# Schematic.net
KiCad netlist of a schematic drawn in Altium Designer
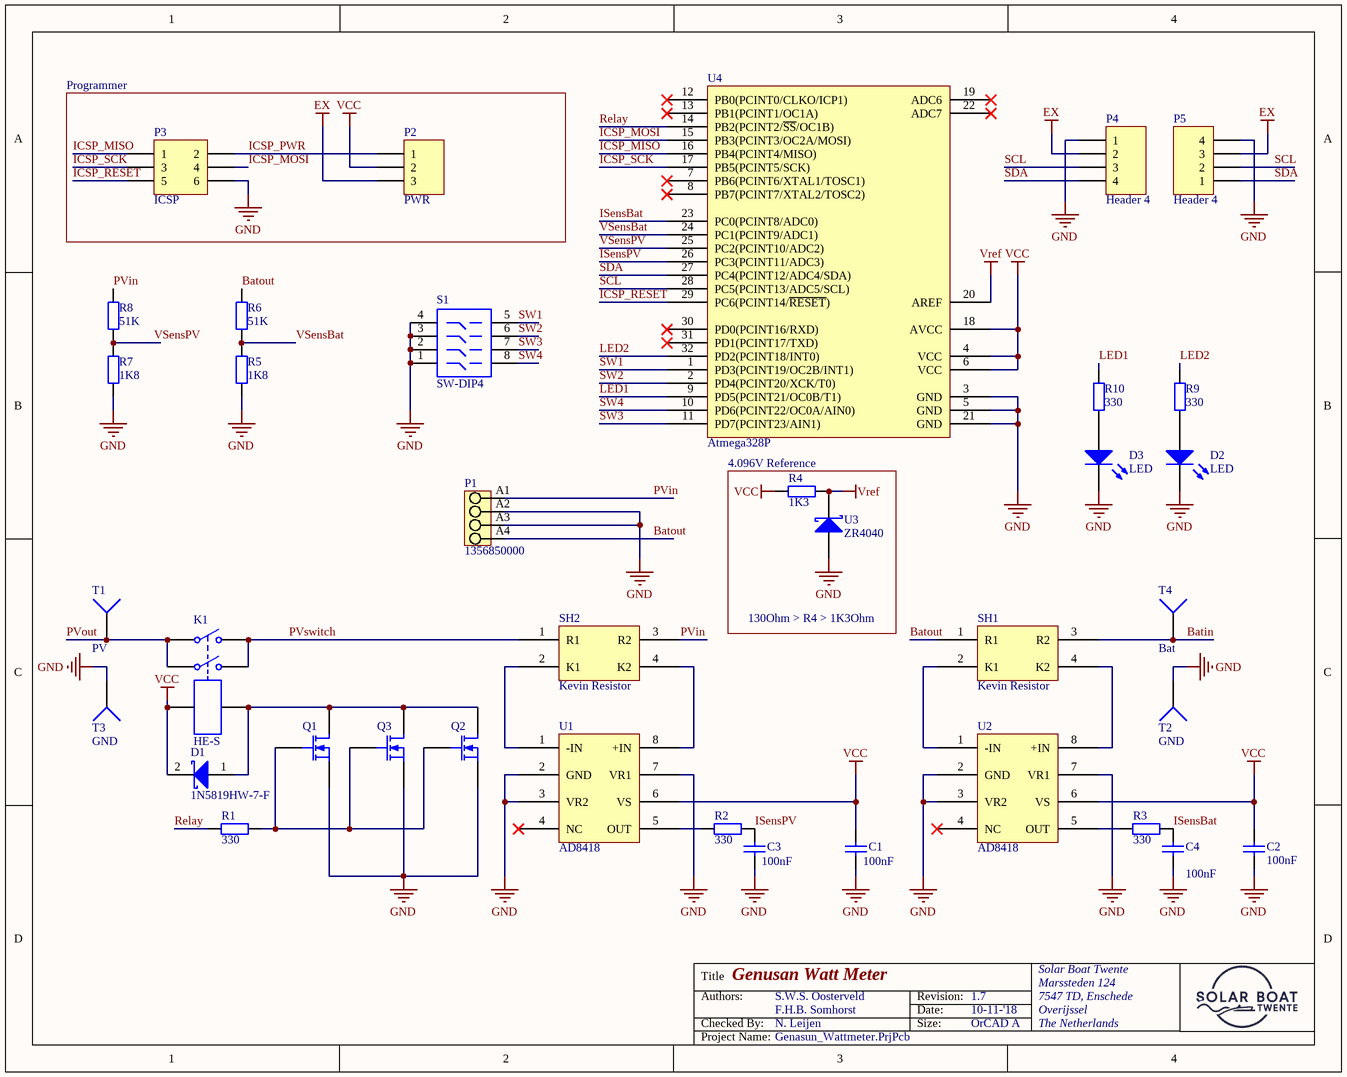
[diagram p0: Schematic.SchDoc]

(export (version "E")
  (design (tool "Eeschema 10.0.6"))
  (components
    (comp (ref "C1")
      (value "100nF")
      (footprint "CAP 0805/2012")
      (description "Capacitor")
      (fields (field (name "Comment") "Cap") (field (name "PUBLISHER") "Altium Limited"))
      (libsource (lib "Miscellaneous Devices") (part "Cap"))
    )
    (comp (ref "C2")
      (value "100nF")
      (footprint "CAP 0805/2012")
      (description "Capacitor")
      (fields (field (name "Comment") "Cap") (field (name "PUBLISHER") "Altium Limited"))
      (libsource (lib "Miscellaneous Devices") (part "Cap"))
    )
    (comp (ref "C3")
      (value "100nF")
      (footprint "CAP 0805/2012")
      (description "Capacitor")
      (fields (field (name "Comment") "Cap") (field (name "PUBLISHER") "Altium Limited"))
      (libsource (lib "Miscellaneous Devices") (part "Cap"))
    )
    (comp (ref "C4")
      (value "100nF")
      (footprint "CAP 0805/2012")
      (description "Capacitor")
      (fields (field (name "Comment") "Cap") (field (name "PUBLISHER") "Altium Limited"))
      (libsource (lib "Miscellaneous Devices") (part "Cap"))
    )
    (comp (ref "D1")
      (value "1N5819HW-7-F")
      (footprint "DIOD-SOD-123-2_V")
      (fields (field (name "MANUFACTURER") "Diodes Inc"))
      (libsource (lib "Altium Content Vault") (part "DIOD-DSKY-A1K2-2"))
    )
    (comp (ref "D2")
      (value "LED")
      (footprint "LED 0805/2012 RED")
      (description "Typical INFRARED GaAs LED")
      (fields (field (name "PUBLISHER") "Altium Limited"))
      (libsource (lib "Miscellaneous Devices") (part "LED0"))
    )
    (comp (ref "D3")
      (value "LED")
      (footprint "LED 0805/2012 RED")
      (description "Typical INFRARED GaAs LED")
      (fields (field (name "PUBLISHER") "Altium Limited"))
      (libsource (lib "Miscellaneous Devices") (part "LED0"))
    )
    (comp (ref "K1")
      (value "HE-S")
      (footprint "Relay HE-S Parasonic")
      (description "Dual-Pole Single-Throw Relay")
      (fields (field (name "PUBLISHER") "Altium Limited"))
      (libsource (lib "Miscellaneous Devices") (part "Relay-DPST"))
    )
    (comp (ref "P1")
      (value "1356850000")
      (footprint "LL_6_35_90V_04")
      (description "OMNIMATE Signal - series LL")
      (fields (field (name "MANUFACTURER") "Weidmueller"))
      (libsource (lib "Altium Content Vault") (part "Terminal_04_1x04"))
    )
    (comp (ref "P2")
      (value "PWR")
      (footprint "HDR1X3")
      (description "Header, 3-Pin")
      (fields (field (name "PUBLISHER") "Altium Limited"))
      (libsource (lib "Miscellaneous Connectors") (part "Header 3"))
    )
    (comp (ref "P3")
      (value "ICSP")
      (footprint "HDR2X3")
      (description "Header, 3-Pin, Dual row")
      (fields (field (name "PUBLISHER") "Altium Limited"))
      (libsource (lib "Miscellaneous Connectors") (part "Header 3X2"))
    )
    (comp (ref "P4")
      (value "Header 4")
      (footprint "TE 282834-4")
      (description "Header, 4-Pin")
      (fields (field (name "PUBLISHER") "Altium Limited"))
      (libsource (lib "Miscellaneous Connectors") (part "Header 4"))
    )
    (comp (ref "P5")
      (value "Header 4")
      (footprint "TE 282834-4")
      (description "Header, 4-Pin")
      (fields (field (name "PUBLISHER") "Altium Limited"))
      (libsource (lib "") (part "Header 4_1"))
    )
    (comp (ref "Q1")
      (value "MOSFET-N")
      (footprint "DIODES SOT-23-3")
      (description "N-Channel MOSFET")
      (fields (field (name "PUBLISHER") "Altium Limited"))
      (libsource (lib "Miscellaneous Devices") (part "MOSFET-N"))
    )
    (comp (ref "Q2")
      (value "MOSFET-N")
      (footprint "DIODES SOT-23-3")
      (description "N-Channel MOSFET")
      (fields (field (name "PUBLISHER") "Altium Limited"))
      (libsource (lib "Miscellaneous Devices") (part "MOSFET-N"))
    )
    (comp (ref "Q3")
      (value "MOSFET-N")
      (footprint "DIODES SOT-23-3")
      (description "N-Channel MOSFET")
      (fields (field (name "PUBLISHER") "Altium Limited"))
      (libsource (lib "Miscellaneous Devices") (part "MOSFET-N"))
    )
    (comp (ref "R1")
      (value "330")
      (footprint "RES 0805/2012")
      (description "Resistor")
      (fields (field (name "Comment") "Res2") (field (name "PUBLISHER") "Altium Limited"))
      (libsource (lib "") (part "Res2_1"))
    )
    (comp (ref "R2")
      (value "330")
      (footprint "RES 0805/2012")
      (description "Resistor")
      (fields (field (name "Comment") "Res2") (field (name "PUBLISHER") "Altium Limited"))
      (libsource (lib "") (part "Res2_1"))
    )
    (comp (ref "R3")
      (value "330")
      (footprint "RES 0805/2012")
      (description "Resistor")
      (fields (field (name "Comment") "Res2") (field (name "PUBLISHER") "Altium Limited"))
      (libsource (lib "") (part "Res2_1"))
    )
    (comp (ref "R4")
      (value "1K3")
      (footprint "RES 0805/2012")
      (description "Resistor")
      (fields (field (name "Comment") "Res2") (field (name "PUBLISHER") "Altium Limited"))
      (libsource (lib "") (part "Res2_1"))
    )
    (comp (ref "R5")
      (value "1K8")
      (footprint "RES 0805/2012")
      (description "Resistor")
      (fields (field (name "Comment") "Res2") (field (name "PUBLISHER") "Altium Limited"))
      (libsource (lib "Miscellaneous Devices") (part "Res2"))
    )
    (comp (ref "R6")
      (value "51K")
      (footprint "RES 0805/2012")
      (description "Resistor")
      (fields (field (name "Comment") "Res2") (field (name "PUBLISHER") "Altium Limited"))
      (libsource (lib "Miscellaneous Devices") (part "Res2"))
    )
    (comp (ref "R7")
      (value "1K8")
      (footprint "RES 0805/2012")
      (description "Resistor")
      (fields (field (name "Comment") "Res2") (field (name "PUBLISHER") "Altium Limited"))
      (libsource (lib "Miscellaneous Devices") (part "Res2"))
    )
    (comp (ref "R8")
      (value "51K")
      (footprint "RES 0805/2012")
      (description "Resistor")
      (fields (field (name "Comment") "Res2") (field (name "PUBLISHER") "Altium Limited"))
      (libsource (lib "Miscellaneous Devices") (part "Res2"))
    )
    (comp (ref "R9")
      (value "330")
      (footprint "RES 0805/2012")
      (description "Resistor")
      (fields (field (name "Comment") "Res2") (field (name "PUBLISHER") "Altium Limited"))
      (libsource (lib "Miscellaneous Devices") (part "Res2"))
    )
    (comp (ref "R10")
      (value "330")
      (footprint "RES 0805/2012")
      (description "Resistor")
      (fields (field (name "Comment") "Res2") (field (name "PUBLISHER") "Altium Limited"))
      (libsource (lib "Miscellaneous Devices") (part "Res2"))
    )
    (comp (ref "S1")
      (value "SW-DIP4")
      (footprint "DIP-8")
      (description "DIP Switch")
      (fields (field (name "PUBLISHER") "Altium Limited"))
      (libsource (lib "Miscellaneous Devices") (part "SW-DIP4"))
    )
    (comp (ref "SH1")
      (value "Kevin Resistor")
      (footprint "TE TLR Shunt")
      (libsource (lib "Personal Library") (part "Kevin Resistor"))
    )
    (comp (ref "SH2")
      (value "Kevin Resistor")
      (footprint "TE TLR Shunt")
      (libsource (lib "Personal Library") (part "Kevin Resistor"))
    )
    (comp (ref "T1")
      (value "PV")
      (footprint "PCB_Pin_Outsteeksel")
      (description "Socket")
      (fields (field (name "PUBLISHER") "Altium Limited"))
      (libsource (lib "Miscellaneous Connectors") (part "Socket"))
    )
    (comp (ref "T2")
      (value "GND")
      (footprint "PCB_Pin_Outsteeksel")
      (description "Socket")
      (fields (field (name "PUBLISHER") "Altium Limited"))
      (libsource (lib "Miscellaneous Connectors") (part "Socket"))
    )
    (comp (ref "T3")
      (value "GND")
      (footprint "PCB_Pin_Outsteeksel")
      (description "Socket")
      (fields (field (name "PUBLISHER") "Altium Limited"))
      (libsource (lib "Miscellaneous Connectors") (part "Socket"))
    )
    (comp (ref "T4")
      (value "Bat")
      (footprint "PCB_Pin_Outsteeksel")
      (description "Socket")
      (fields (field (name "PUBLISHER") "Altium Limited"))
      (libsource (lib "Miscellaneous Connectors") (part "Socket"))
    )
    (comp (ref "U1")
      (value "AD8418")
      (footprint "INTERSIL MSOP-8 M8.118")
      (libsource (lib "GJ24") (part "AD8418"))
    )
    (comp (ref "U2")
      (value "AD8418")
      (footprint "INTERSIL MSOP-8 M8.118")
      (libsource (lib "GJ24") (part "AD8418"))
    )
    (comp (ref "U3")
      (value "ZR4040")
      (footprint "DIODES SOT-23-3")
      (description "Schottky Rectifier")
      (fields (field (name "PUBLISHER") "Altium Limited"))
      (libsource (lib "Miscellaneous Devices") (part "Diode 10TQ035"))
    )
    (comp (ref "U4")
      (value "Atmega328P")
      (footprint "ST LQFP-32 7X7MM")
      (libsource (lib "GJ24") (part "Atmega328P"))
    )
  )
  (nets
    (net (code "1") (name "/Batin") (class "Default")
      (node (ref "SH1") (pin "3") (pinfunction "R2_3") (pintype "passive"))
      (node (ref "T4") (pin "1") (pinfunction "1_1") (pintype "passive"))
    )
    (net (code "2") (name "/Batout") (class "Default")
      (node (ref "P1") (pin "A4") (pinfunction "A4_A4") (pintype "passive"))
      (node (ref "R6") (pin "2") (pinfunction "2_2") (pintype "passive"))
      (node (ref "SH1") (pin "1") (pinfunction "R1_1") (pintype "passive"))
    )
    (net (code "3") (name "/ICSP_MISO") (class "Default")
      (node (ref "P3") (pin "1") (pinfunction "1_1") (pintype "passive"))
      (node (ref "U4") (pin "16") (pinfunction "PB4(PCINT4/MISO)_16") (pintype "passive"))
    )
    (net (code "4") (name "/ICSP_MOSI") (class "Default")
      (node (ref "P3") (pin "4") (pinfunction "4_4") (pintype "passive"))
      (node (ref "U4") (pin "15") (pinfunction "PB3(PCINT3/OC2A/MOSI)_15") (pintype "passive"))
    )
    (net (code "5") (name "/ICSP_PWR") (class "Default")
      (node (ref "P2") (pin "1") (pinfunction "1_1") (pintype "passive"))
      (node (ref "P3") (pin "2") (pinfunction "2_2") (pintype "passive"))
    )
    (net (code "6") (name "/ICSP_RESET") (class "Default")
      (node (ref "P3") (pin "5") (pinfunction "5_5") (pintype "passive"))
      (node (ref "U4") (pin "29") (pinfunction "PC6(PCINT14/~{RESET})_29") (pintype "passive"))
    )
    (net (code "7") (name "/ICSP_SCK") (class "Default")
      (node (ref "P3") (pin "3") (pinfunction "3_3") (pintype "passive"))
      (node (ref "U4") (pin "17") (pinfunction "PB5(PCINT5/SCK)_17") (pintype "passive"))
    )
    (net (code "8") (name "/ISensBat") (class "Default")
      (node (ref "C4") (pin "2") (pinfunction "2_2") (pintype "passive"))
      (node (ref "R3") (pin "1") (pinfunction "1_1") (pintype "passive"))
      (node (ref "U4") (pin "23") (pinfunction "PC0(PCINT8/ADC0)_23") (pintype "passive"))
    )
    (net (code "9") (name "/ISensPV") (class "Default")
      (node (ref "C3") (pin "2") (pinfunction "2_2") (pintype "passive"))
      (node (ref "R2") (pin "1") (pinfunction "1_1") (pintype "passive"))
      (node (ref "U4") (pin "26") (pinfunction "PC3(PCINT11/ADC3)_26") (pintype "passive"))
    )
    (net (code "10") (name "/LED1") (class "Default")
      (node (ref "R10") (pin "2") (pinfunction "2_2") (pintype "passive"))
      (node (ref "U4") (pin "9") (pinfunction "PD5(PCINT21/OC0B/T1)_9") (pintype "passive"))
    )
    (net (code "11") (name "/LED2") (class "Default")
      (node (ref "R9") (pin "2") (pinfunction "2_2") (pintype "passive"))
      (node (ref "U4") (pin "32") (pinfunction "PD2(PCINT18/INT0)_32") (pintype "passive"))
    )
    (net (code "12") (name "/PVin") (class "Default")
      (node (ref "P1") (pin "A1") (pinfunction "A1_A1") (pintype "passive"))
      (node (ref "R8") (pin "2") (pinfunction "2_2") (pintype "passive"))
      (node (ref "SH2") (pin "3") (pinfunction "R2_3") (pintype "passive"))
    )
    (net (code "13") (name "/PVout") (class "Default")
      (node (ref "K1") (pin "1") (pinfunction "1_1") (pintype "passive"))
      (node (ref "K1") (pin "3") (pinfunction "3_3") (pintype "passive"))
      (node (ref "T1") (pin "1") (pinfunction "1_1") (pintype "passive"))
    )
    (net (code "14") (name "/PVswitch") (class "Default")
      (node (ref "K1") (pin "2") (pinfunction "2_2") (pintype "passive"))
      (node (ref "K1") (pin "4") (pinfunction "4_4") (pintype "passive"))
      (node (ref "SH2") (pin "1") (pinfunction "R1_1") (pintype "passive"))
    )
    (net (code "15") (name "/Relay") (class "Default")
      (node (ref "R1") (pin "2") (pinfunction "2_2") (pintype "passive"))
      (node (ref "U4") (pin "14") (pinfunction "PB2(PCINT2/~{SS}/OC1B)_14") (pintype "passive"))
    )
    (net (code "16") (name "/SCL") (class "Default")
      (node (ref "P4") (pin "3") (pinfunction "3_3") (pintype "passive"))
      (node (ref "P5") (pin "2") (pinfunction "2_2") (pintype "passive"))
      (node (ref "U4") (pin "28") (pinfunction "PC5(PCINT13/ADC5/SCL)_28") (pintype "passive"))
    )
    (net (code "17") (name "/SDA") (class "Default")
      (node (ref "P4") (pin "4") (pinfunction "4_4") (pintype "passive"))
      (node (ref "P5") (pin "1") (pinfunction "1_1") (pintype "passive"))
      (node (ref "U4") (pin "27") (pinfunction "PC4(PCINT12/ADC4/SDA)_27") (pintype "passive"))
    )
    (net (code "18") (name "/SW1") (class "Default")
      (node (ref "S1") (pin "5") (pinfunction "5_5") (pintype "passive"))
      (node (ref "U4") (pin "1") (pinfunction "PD3(PCINT19/OC2B/INT1)_1") (pintype "passive"))
    )
    (net (code "19") (name "/SW2") (class "Default")
      (node (ref "S1") (pin "6") (pinfunction "6_6") (pintype "passive"))
      (node (ref "U4") (pin "2") (pinfunction "PD4(PCINT20/XCK/T0)_2") (pintype "passive"))
    )
    (net (code "20") (name "/SW3") (class "Default")
      (node (ref "S1") (pin "7") (pinfunction "7_7") (pintype "passive"))
      (node (ref "U4") (pin "11") (pinfunction "PD7(PCINT23/AIN1)_11") (pintype "passive"))
    )
    (net (code "21") (name "/SW4") (class "Default")
      (node (ref "S1") (pin "8") (pinfunction "8_8") (pintype "passive"))
      (node (ref "U4") (pin "10") (pinfunction "PD6(PCINT22/OC0A/AIN0)_10") (pintype "passive"))
    )
    (net (code "22") (name "/VSensBat") (class "Default")
      (node (ref "R5") (pin "2") (pinfunction "2_2") (pintype "passive"))
      (node (ref "R6") (pin "1") (pinfunction "1_1") (pintype "passive"))
      (node (ref "U4") (pin "24") (pinfunction "PC1(PCINT9/ADC1)_24") (pintype "passive"))
    )
    (net (code "23") (name "/VSensPV") (class "Default")
      (node (ref "R7") (pin "2") (pinfunction "2_2") (pintype "passive"))
      (node (ref "R8") (pin "1") (pinfunction "1_1") (pintype "passive"))
      (node (ref "U4") (pin "25") (pinfunction "PC2(PCINT10/ADC2)_25") (pintype "passive"))
    )
    (net (code "24") (name "EX") (class "Default")
      (node (ref "P2") (pin "3") (pinfunction "3_3") (pintype "passive"))
      (node (ref "P4") (pin "2") (pinfunction "2_2") (pintype "passive"))
      (node (ref "P5") (pin "3") (pinfunction "3_3") (pintype "passive"))
    )
    (net (code "25") (name "GND") (class "Default")
      (node (ref "C1") (pin "1") (pinfunction "1_1") (pintype "passive"))
      (node (ref "C2") (pin "2") (pinfunction "2_2") (pintype "passive"))
      (node (ref "C3") (pin "1") (pinfunction "1_1") (pintype "passive"))
      (node (ref "C4") (pin "1") (pinfunction "1_1") (pintype "passive"))
      (node (ref "D2") (pin "2") (pinfunction "K_2") (pintype "passive"))
      (node (ref "D3") (pin "2") (pinfunction "K_2") (pintype "passive"))
      (node (ref "P1") (pin "A2") (pinfunction "A2_A2") (pintype "passive"))
      (node (ref "P1") (pin "A3") (pinfunction "A3_A3") (pintype "passive"))
      (node (ref "P3") (pin "6") (pinfunction "6_6") (pintype "passive"))
      (node (ref "P4") (pin "1") (pinfunction "1_1") (pintype "passive"))
      (node (ref "P5") (pin "4") (pinfunction "4_4") (pintype "passive"))
      (node (ref "Q1") (pin "2") (pinfunction "S_2") (pintype "passive"))
      (node (ref "Q2") (pin "2") (pinfunction "S_2") (pintype "passive"))
      (node (ref "Q3") (pin "2") (pinfunction "S_2") (pintype "passive"))
      (node (ref "R5") (pin "1") (pinfunction "1_1") (pintype "passive"))
      (node (ref "R7") (pin "1") (pinfunction "1_1") (pintype "passive"))
      (node (ref "S1") (pin "1") (pinfunction "1_1") (pintype "passive"))
      (node (ref "S1") (pin "2") (pinfunction "2_2") (pintype "passive"))
      (node (ref "S1") (pin "3") (pinfunction "3_3") (pintype "passive"))
      (node (ref "S1") (pin "4") (pinfunction "4_4") (pintype "passive"))
      (node (ref "T2") (pin "1") (pinfunction "1_1") (pintype "passive"))
      (node (ref "T3") (pin "1") (pinfunction "1_1") (pintype "passive"))
      (node (ref "U1") (pin "2") (pinfunction "GND_2") (pintype "passive"))
      (node (ref "U1") (pin "3") (pinfunction "VR2_3") (pintype "passive"))
      (node (ref "U1") (pin "7") (pinfunction "VR1_7") (pintype "passive"))
      (node (ref "U2") (pin "2") (pinfunction "GND_2") (pintype "passive"))
      (node (ref "U2") (pin "3") (pinfunction "VR2_3") (pintype "passive"))
      (node (ref "U2") (pin "7") (pinfunction "VR1_7") (pintype "passive"))
      (node (ref "U3") (pin "3") (pinfunction "A_3") (pintype "passive"))
      (node (ref "U4") (pin "21") (pinfunction "GND_21") (pintype "passive"))
      (node (ref "U4") (pin "3") (pinfunction "GND_3") (pintype "passive"))
      (node (ref "U4") (pin "5") (pinfunction "GND_5") (pintype "passive"))
    )
    (net (code "26") (name "Net-(D1-A)") (class "Default")
      (node (ref "D1") (pin "1") (pinfunction "A_1") (pintype "passive"))
      (node (ref "K1") (pin "6") (pinfunction "6_6") (pintype "passive"))
      (node (ref "Q1") (pin "1") (pinfunction "D_1") (pintype "passive"))
      (node (ref "Q2") (pin "1") (pinfunction "D_1") (pintype "passive"))
      (node (ref "Q3") (pin "1") (pinfunction "D_1") (pintype "passive"))
    )
    (net (code "27") (name "Net-(D2-A)") (class "Default")
      (node (ref "D2") (pin "1") (pinfunction "A_1") (pintype "passive"))
      (node (ref "R9") (pin "1") (pinfunction "1_1") (pintype "passive"))
    )
    (net (code "28") (name "Net-(D3-A)") (class "Default")
      (node (ref "D3") (pin "1") (pinfunction "A_1") (pintype "passive"))
      (node (ref "R10") (pin "1") (pinfunction "1_1") (pintype "passive"))
    )
    (net (code "29") (name "Net-(Q1-G)") (class "Default")
      (node (ref "Q1") (pin "3") (pinfunction "G_3") (pintype "passive"))
      (node (ref "Q2") (pin "3") (pinfunction "G_3") (pintype "passive"))
      (node (ref "Q3") (pin "3") (pinfunction "G_3") (pintype "passive"))
      (node (ref "R1") (pin "1") (pinfunction "1_1") (pintype "passive"))
    )
    (net (code "30") (name "Net-(SH1-K1)") (class "Default")
      (node (ref "SH1") (pin "2") (pinfunction "K1_2") (pintype "passive"))
      (node (ref "U2") (pin "1") (pinfunction "-IN_1") (pintype "passive"))
    )
    (net (code "31") (name "Net-(SH1-K2)") (class "Default")
      (node (ref "SH1") (pin "4") (pinfunction "K2_4") (pintype "passive"))
      (node (ref "U2") (pin "8") (pinfunction "+IN_8") (pintype "passive"))
    )
    (net (code "32") (name "Net-(SH2-K1)") (class "Default")
      (node (ref "SH2") (pin "2") (pinfunction "K1_2") (pintype "passive"))
      (node (ref "U1") (pin "1") (pinfunction "-IN_1") (pintype "passive"))
    )
    (net (code "33") (name "Net-(SH2-K2)") (class "Default")
      (node (ref "SH2") (pin "4") (pinfunction "K2_4") (pintype "passive"))
      (node (ref "U1") (pin "8") (pinfunction "+IN_8") (pintype "passive"))
    )
    (net (code "34") (name "Net-(U1-OUT)") (class "Default")
      (node (ref "R2") (pin "2") (pinfunction "2_2") (pintype "passive"))
      (node (ref "U1") (pin "5") (pinfunction "OUT_5") (pintype "passive"))
    )
    (net (code "35") (name "Net-(U2-OUT)") (class "Default")
      (node (ref "R3") (pin "2") (pinfunction "2_2") (pintype "passive"))
      (node (ref "U2") (pin "5") (pinfunction "OUT_5") (pintype "passive"))
    )
    (net (code "36") (name "VCC") (class "Default")
      (node (ref "C1") (pin "2") (pinfunction "2_2") (pintype "passive"))
      (node (ref "C2") (pin "1") (pinfunction "1_1") (pintype "passive"))
      (node (ref "D1") (pin "2") (pinfunction "K_2") (pintype "passive"))
      (node (ref "K1") (pin "5") (pinfunction "5_5") (pintype "passive"))
      (node (ref "P2") (pin "2") (pinfunction "2_2") (pintype "passive"))
      (node (ref "R4") (pin "2") (pinfunction "2_2") (pintype "passive"))
      (node (ref "U1") (pin "6") (pinfunction "VS_6") (pintype "passive"))
      (node (ref "U2") (pin "6") (pinfunction "VS_6") (pintype "passive"))
      (node (ref "U4") (pin "18") (pinfunction "AVCC_18") (pintype "passive"))
      (node (ref "U4") (pin "4") (pinfunction "VCC_4") (pintype "passive"))
      (node (ref "U4") (pin "6") (pinfunction "VCC_6") (pintype "passive"))
    )
    (net (code "37") (name "Vref") (class "Default")
      (node (ref "R4") (pin "1") (pinfunction "1_1") (pintype "passive"))
      (node (ref "U3") (pin "1") (pinfunction "K_1") (pintype "passive"))
      (node (ref "U4") (pin "20") (pinfunction "AREF_20") (pintype "passive"))
    )
    (net (code "38") (name "unconnected-(U1-NC-Pad4)") (class "Default")
      (node (ref "U1") (pin "4") (pinfunction "NC_4") (pintype "passive+no_connect"))
    )
    (net (code "39") (name "unconnected-(U2-NC-Pad4)") (class "Default")
      (node (ref "U2") (pin "4") (pinfunction "NC_4") (pintype "passive+no_connect"))
    )
    (net (code "40") (name "unconnected-(U4-ADC6-Pad19)") (class "Default")
      (node (ref "U4") (pin "19") (pinfunction "ADC6_19") (pintype "passive+no_connect"))
    )
    (net (code "41") (name "unconnected-(U4-ADC7-Pad22)") (class "Default")
      (node (ref "U4") (pin "22") (pinfunction "ADC7_22") (pintype "passive+no_connect"))
    )
    (net (code "42") (name "unconnected-(U4-PB0(PCINT0{slash}CLKO{slash}ICP1)-Pad12)") (class "Default")
      (node (ref "U4") (pin "12") (pinfunction "PB0(PCINT0/CLKO/ICP1)_12") (pintype "passive+no_connect"))
    )
    (net (code "43") (name "unconnected-(U4-PB1(PCINT1{slash}OC1A)-Pad13)") (class "Default")
      (node (ref "U4") (pin "13") (pinfunction "PB1(PCINT1/OC1A)_13") (pintype "passive+no_connect"))
    )
    (net (code "44") (name "unconnected-(U4-PB6(PCINT6{slash}XTAL1{slash}TOSC1)-Pad7)") (class "Default")
      (node (ref "U4") (pin "7") (pinfunction "PB6(PCINT6/XTAL1/TOSC1)_7") (pintype "passive+no_connect"))
    )
    (net (code "45") (name "unconnected-(U4-PB7(PCINT7{slash}XTAL2{slash}TOSC2)-Pad8)") (class "Default")
      (node (ref "U4") (pin "8") (pinfunction "PB7(PCINT7/XTAL2/TOSC2)_8") (pintype "passive+no_connect"))
    )
    (net (code "46") (name "unconnected-(U4-PD0(PCINT16{slash}RXD)-Pad30)") (class "Default")
      (node (ref "U4") (pin "30") (pinfunction "PD0(PCINT16/RXD)_30") (pintype "passive+no_connect"))
    )
    (net (code "47") (name "unconnected-(U4-PD1(PCINT17{slash}TXD)-Pad31)") (class "Default")
      (node (ref "U4") (pin "31") (pinfunction "PD1(PCINT17/TXD)_31") (pintype "passive+no_connect"))
    )
  )
)
